# design.net
KiCad netlist of a schematic drawn in EasyEDA Pro
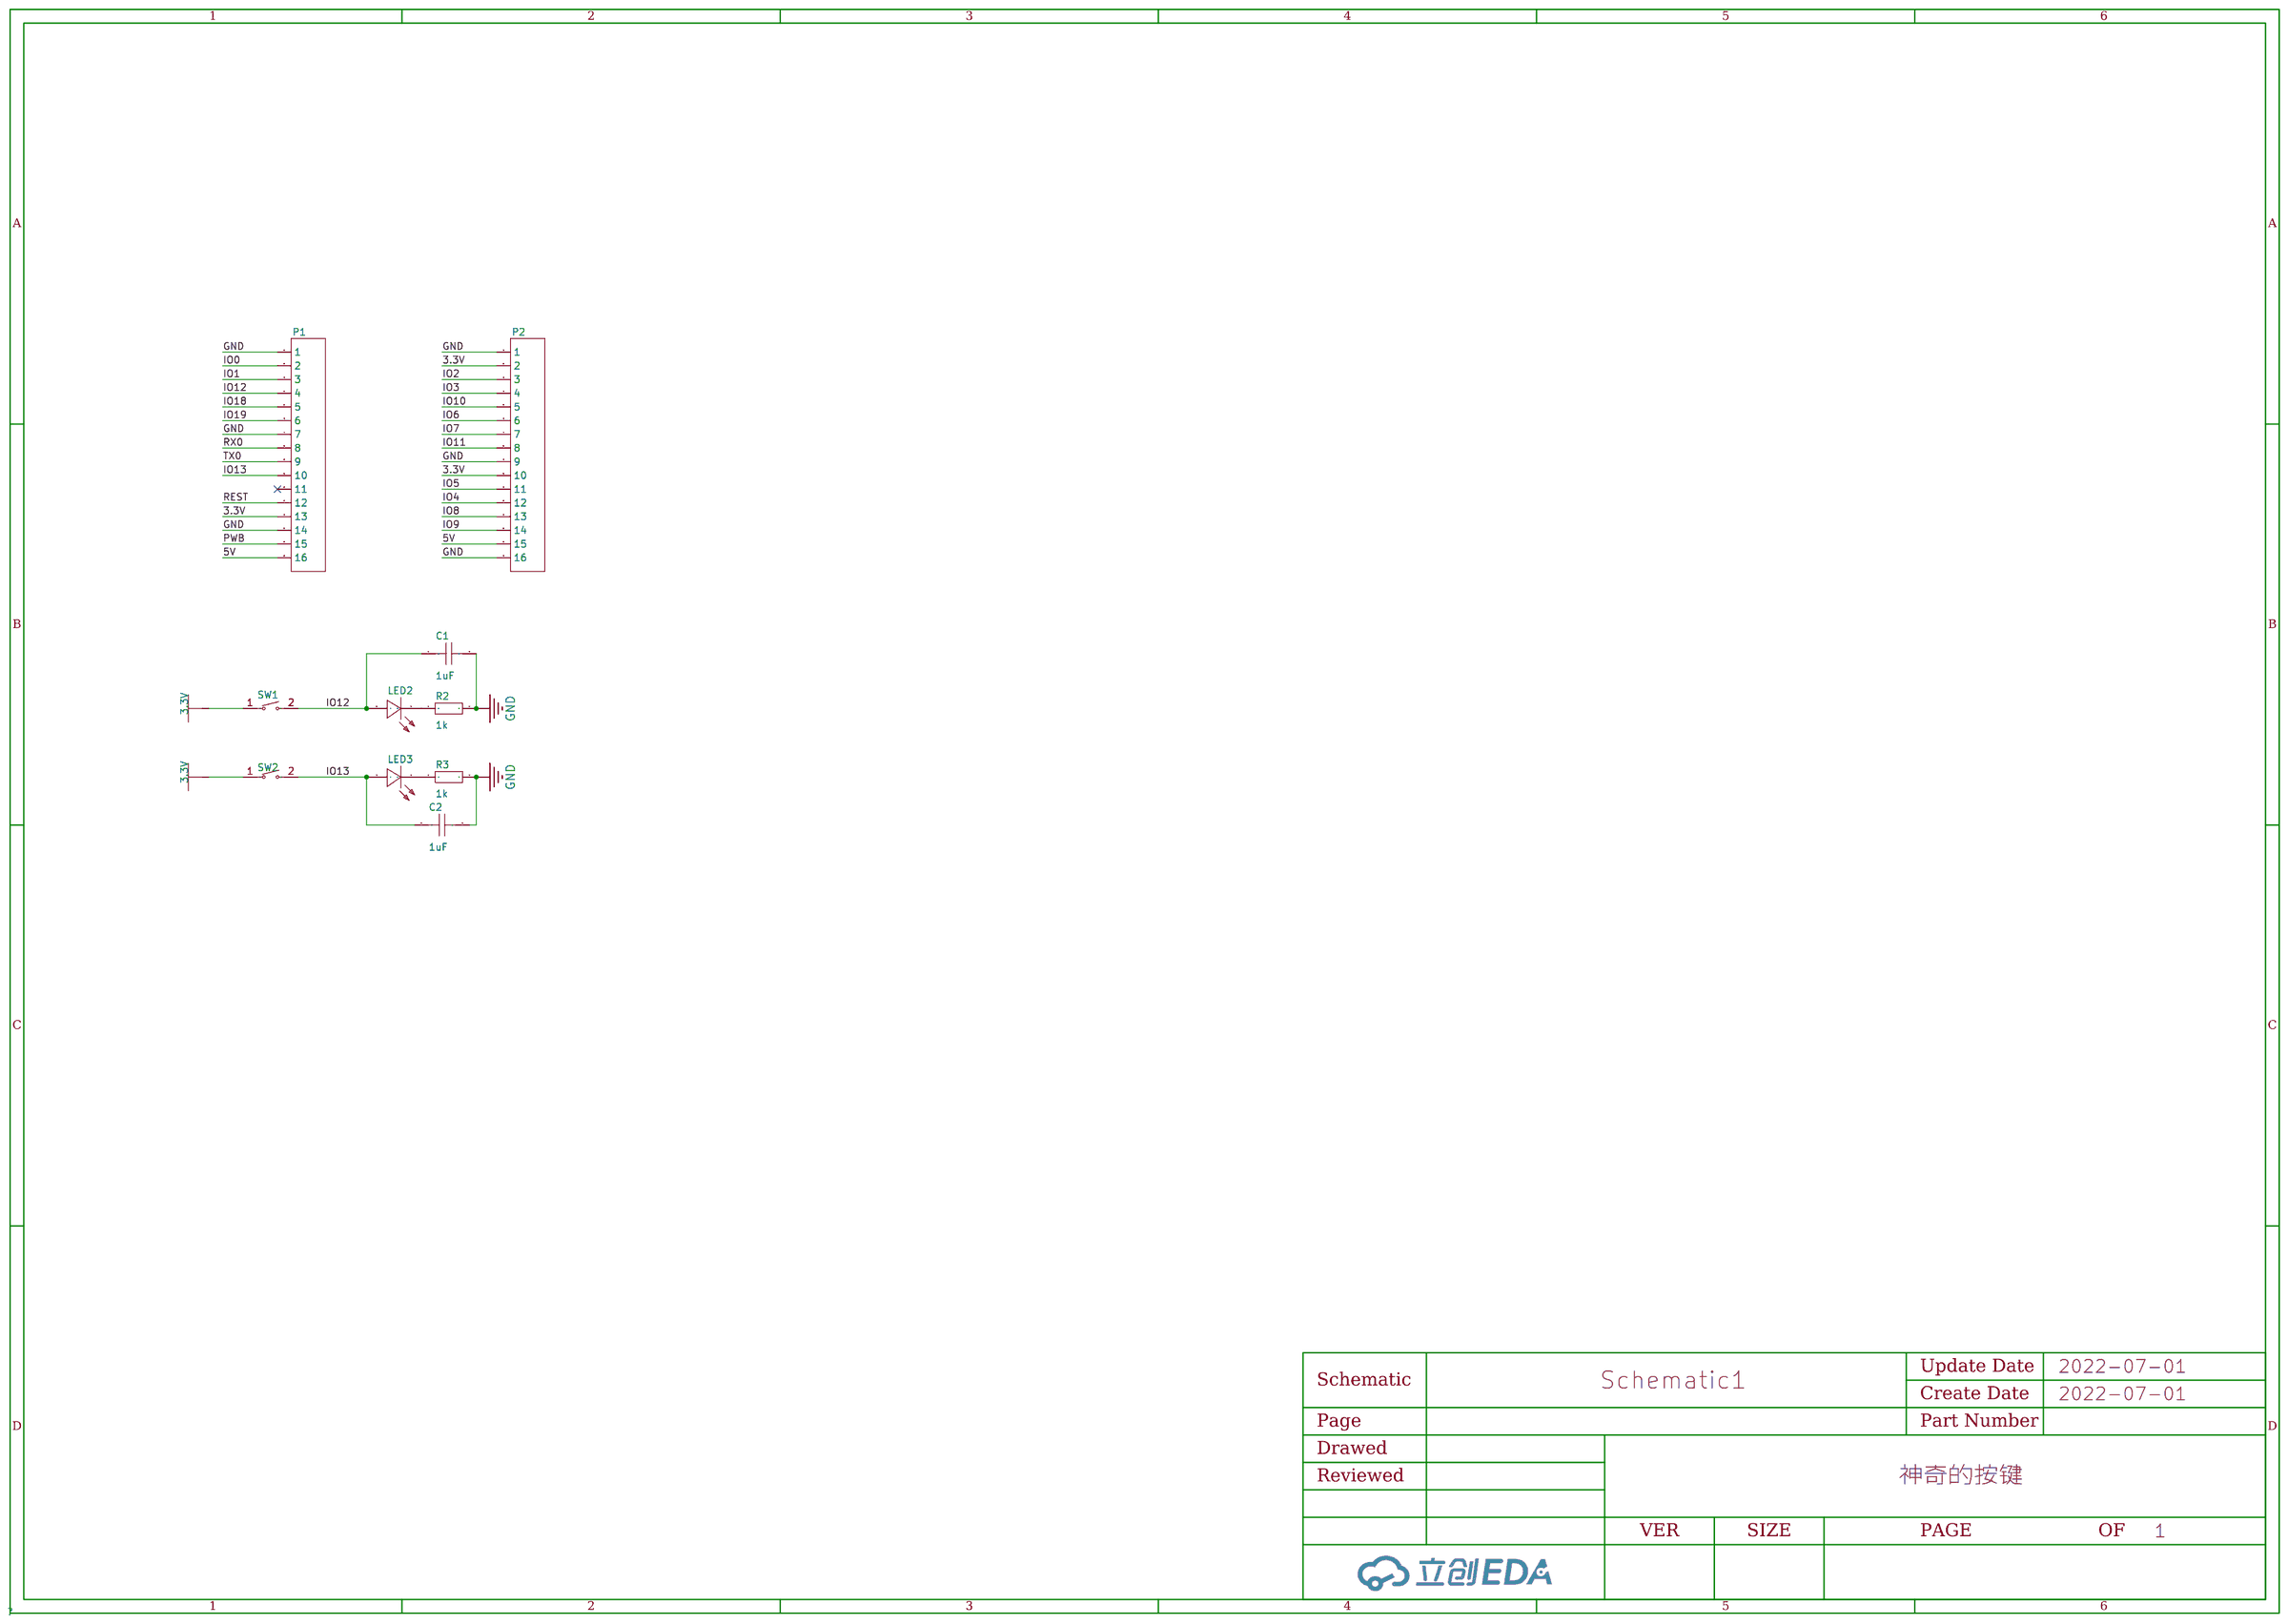
[diagram p0: schematic sheet]

(export (version "E")
  (design (tool "Eeschema 10.0.6"))
  (components
    (comp (ref "C1")
      (value "1uF")
      (footprint "easyedapro:C1206")
      (description "容值:1uF;精度:±10%;额定电压:50V;温度系数:X7R;")
      (fields
        (field (name "Manufacturer Part") "CL31B105KBHNNNE")
        (field (name "Manufacturer") "SAMSUNG(三星)")
      )
      (libsource (lib "easyedapro") (part "CL31B105KBHNNNE"))
    )
    (comp (ref "C2")
      (value "1uF")
      (footprint "easyedapro:C1206")
      (description "容值:1uF;精度:±10%;额定电压:50V;温度系数:X7R;")
      (fields
        (field (name "Manufacturer Part") "CL31B105KBHNNNE")
        (field (name "Manufacturer") "SAMSUNG(三星)")
      )
      (libsource (lib "easyedapro") (part "CL31B105KBHNNNE"))
    )
    (comp (ref "LED2")
      (value "~")
      (footprint "easyedapro:LED1206-RD_ORANGE")
      (fields (field (name "Manufacturer Part") "SZYY1206O") (field (name "Manufacturer") "yongyu(永裕光电)"))
      (libsource (lib "easyedapro") (part "SZYY1206O"))
    )
    (comp (ref "LED3")
      (value "~")
      (footprint "easyedapro:LED1206-RD_ORANGE")
      (fields (field (name "Manufacturer Part") "SZYY1206O") (field (name "Manufacturer") "yongyu(永裕光电)"))
      (libsource (lib "easyedapro") (part "SZYY1206O"))
    )
    (comp (ref "P1")
      (value "~")
      (footprint "easyedapro:HDR-TH_16P-P2.54-V-F-1")
      (description "间距:2.54mm;总孔位数:16;排数:1;行距:-;安装类型:直插;塑高:-;触头材质:-;触头镀层:-;")
      (fields (field (name "Manufacturer Part") "2.54-1*16P母") (field (name "Manufacturer") "BOOMELE(博穆精密)"))
      (libsource (lib "easyedapro") (part "Header-Female-2.54_1x16"))
    )
    (comp (ref "P2")
      (value "~")
      (footprint "easyedapro:HDR-TH_16P-P2.54-V-F-1")
      (description "间距:2.54mm;总孔位数:16;排数:1;行距:-;安装类型:直插;塑高:-;触头材质:-;触头镀层:-;")
      (fields (field (name "Manufacturer Part") "2.54-1*16P母") (field (name "Manufacturer") "BOOMELE(博穆精密)"))
      (libsource (lib "easyedapro") (part "Header-Female-2.54_1x16"))
    )
    (comp (ref "R2")
      (value "1k")
      (footprint "easyedapro:R1206")
      (description "电阻类型:厚膜电阻;阻值:1k;精度:±5%;功率:250mW;温度系数:±100ppm/;最大工作电压:200V;工作温度范围:-55~+155;")
      (fields
        (field (name "Manufacturer Part") "1206W4J0102T5E")
        (field (name "Manufacturer") "UNI-ROYAL(厚声)")
      )
      (libsource (lib "easyedapro") (part "1206W4J0102T5E"))
    )
    (comp (ref "R3")
      (value "1k")
      (footprint "easyedapro:R1206")
      (description "电阻类型:厚膜电阻;阻值:1k;精度:±5%;功率:250mW;温度系数:±100ppm/;最大工作电压:200V;工作温度范围:-55~+155;")
      (fields
        (field (name "Manufacturer Part") "1206W4J0102T5E")
        (field (name "Manufacturer") "UNI-ROYAL(厚声)")
      )
      (libsource (lib "easyedapro") (part "1206W4J0102T5E"))
    )
    (comp (ref "SW1")
      (value "~")
      (footprint "easyedapro:SW-TH_CPG151101D9X")
      (fields (field (name "Manufacturer Part") "CPG151101D93") (field (name "Manufacturer") "Kailh(凯华)"))
      (libsource (lib "easyedapro") (part "CPG151101D93"))
    )
    (comp (ref "SW2")
      (value "~")
      (footprint "easyedapro:SW-TH_CPG151101D9X")
      (fields (field (name "Manufacturer Part") "CPG151101D93") (field (name "Manufacturer") "Kailh(凯华)"))
      (libsource (lib "easyedapro") (part "CPG151101D93"))
    )
  )
  (nets
    (net (code "1") (name "/5V") (class "Default")
      (node (ref "P1") (pin "16") (pinfunction "16_16") (pintype "input"))
      (node (ref "P2") (pin "15") (pinfunction "15_15") (pintype "input"))
    )
    (net (code "2") (name "/IO0") (class "Default")
      (node (ref "P1") (pin "2") (pinfunction "2_2") (pintype "input"))
    )
    (net (code "3") (name "/IO1") (class "Default")
      (node (ref "P1") (pin "3") (pinfunction "3_3") (pintype "input"))
    )
    (net (code "4") (name "/IO2") (class "Default")
      (node (ref "P2") (pin "3") (pinfunction "3_3") (pintype "input"))
    )
    (net (code "5") (name "/IO3") (class "Default")
      (node (ref "P2") (pin "4") (pinfunction "4_4") (pintype "input"))
    )
    (net (code "6") (name "/IO4") (class "Default")
      (node (ref "P2") (pin "12") (pinfunction "12_12") (pintype "input"))
    )
    (net (code "7") (name "/IO5") (class "Default")
      (node (ref "P2") (pin "11") (pinfunction "11_11") (pintype "input"))
    )
    (net (code "8") (name "/IO6") (class "Default")
      (node (ref "P2") (pin "6") (pinfunction "6_6") (pintype "input"))
    )
    (net (code "9") (name "/IO7") (class "Default")
      (node (ref "P2") (pin "7") (pinfunction "7_7") (pintype "input"))
    )
    (net (code "10") (name "/IO8") (class "Default")
      (node (ref "P2") (pin "13") (pinfunction "13_13") (pintype "input"))
    )
    (net (code "11") (name "/IO9") (class "Default")
      (node (ref "P2") (pin "14") (pinfunction "14_14") (pintype "input"))
    )
    (net (code "12") (name "/IO10") (class "Default")
      (node (ref "P2") (pin "5") (pinfunction "5_5") (pintype "input"))
    )
    (net (code "13") (name "/IO11") (class "Default")
      (node (ref "P2") (pin "8") (pinfunction "8_8") (pintype "input"))
    )
    (net (code "14") (name "/IO12") (class "Default")
      (node (ref "C1") (pin "1") (pinfunction "1_1") (pintype "input"))
      (node (ref "LED2") (pin "2") (pinfunction "A_2") (pintype "input"))
      (node (ref "P1") (pin "4") (pinfunction "4_4") (pintype "input"))
      (node (ref "SW1") (pin "2") (pinfunction "2_2") (pintype "input"))
    )
    (net (code "15") (name "/IO13") (class "Default")
      (node (ref "C2") (pin "1") (pinfunction "1_1") (pintype "input"))
      (node (ref "LED3") (pin "2") (pinfunction "A_2") (pintype "input"))
      (node (ref "P1") (pin "10") (pinfunction "10_10") (pintype "input"))
      (node (ref "SW2") (pin "2") (pinfunction "2_2") (pintype "input"))
    )
    (net (code "16") (name "/IO18") (class "Default")
      (node (ref "P1") (pin "5") (pinfunction "5_5") (pintype "input"))
    )
    (net (code "17") (name "/IO19") (class "Default")
      (node (ref "P1") (pin "6") (pinfunction "6_6") (pintype "input"))
    )
    (net (code "18") (name "/PWB") (class "Default")
      (node (ref "P1") (pin "15") (pinfunction "15_15") (pintype "input"))
    )
    (net (code "19") (name "/REST") (class "Default")
      (node (ref "P1") (pin "12") (pinfunction "12_12") (pintype "input"))
    )
    (net (code "20") (name "/RX0") (class "Default")
      (node (ref "P1") (pin "8") (pinfunction "8_8") (pintype "input"))
    )
    (net (code "21") (name "/TX0") (class "Default")
      (node (ref "P1") (pin "9") (pinfunction "9_9") (pintype "input"))
    )
    (net (code "22") (name "3.3V") (class "Default")
      (node (ref "P1") (pin "13") (pinfunction "13_13") (pintype "input"))
      (node (ref "P2") (pin "10") (pinfunction "10_10") (pintype "input"))
      (node (ref "P2") (pin "2") (pinfunction "2_2") (pintype "input"))
      (node (ref "SW1") (pin "1") (pinfunction "1_1") (pintype "input"))
      (node (ref "SW2") (pin "1") (pinfunction "1_1") (pintype "input"))
    )
    (net (code "23") (name "GND") (class "Default")
      (node (ref "C1") (pin "2") (pinfunction "2_2") (pintype "input"))
      (node (ref "C2") (pin "2") (pinfunction "2_2") (pintype "input"))
      (node (ref "P1") (pin "1") (pinfunction "1_1") (pintype "input"))
      (node (ref "P1") (pin "14") (pinfunction "14_14") (pintype "input"))
      (node (ref "P1") (pin "7") (pinfunction "7_7") (pintype "input"))
      (node (ref "P2") (pin "1") (pinfunction "1_1") (pintype "input"))
      (node (ref "P2") (pin "16") (pinfunction "16_16") (pintype "input"))
      (node (ref "P2") (pin "9") (pinfunction "9_9") (pintype "input"))
      (node (ref "R2") (pin "2") (pinfunction "2_2") (pintype "input"))
      (node (ref "R3") (pin "2") (pinfunction "2_2") (pintype "input"))
    )
    (net (code "24") (name "Net-(LED2-K)") (class "Default")
      (node (ref "LED2") (pin "1") (pinfunction "K_1") (pintype "input"))
      (node (ref "R2") (pin "1") (pinfunction "1_1") (pintype "input"))
    )
    (net (code "25") (name "Net-(LED3-K)") (class "Default")
      (node (ref "LED3") (pin "1") (pinfunction "K_1") (pintype "input"))
      (node (ref "R3") (pin "1") (pinfunction "1_1") (pintype "input"))
    )
    (net (code "26") (name "unconnected-(P1-Pad11)") (class "Default")
      (node (ref "P1") (pin "11") (pinfunction "11_11") (pintype "input+no_connect"))
    )
  )
)
